# 4ButtonSwitch_Rev1.net
KiCad netlist of a schematic drawn in EAGLE
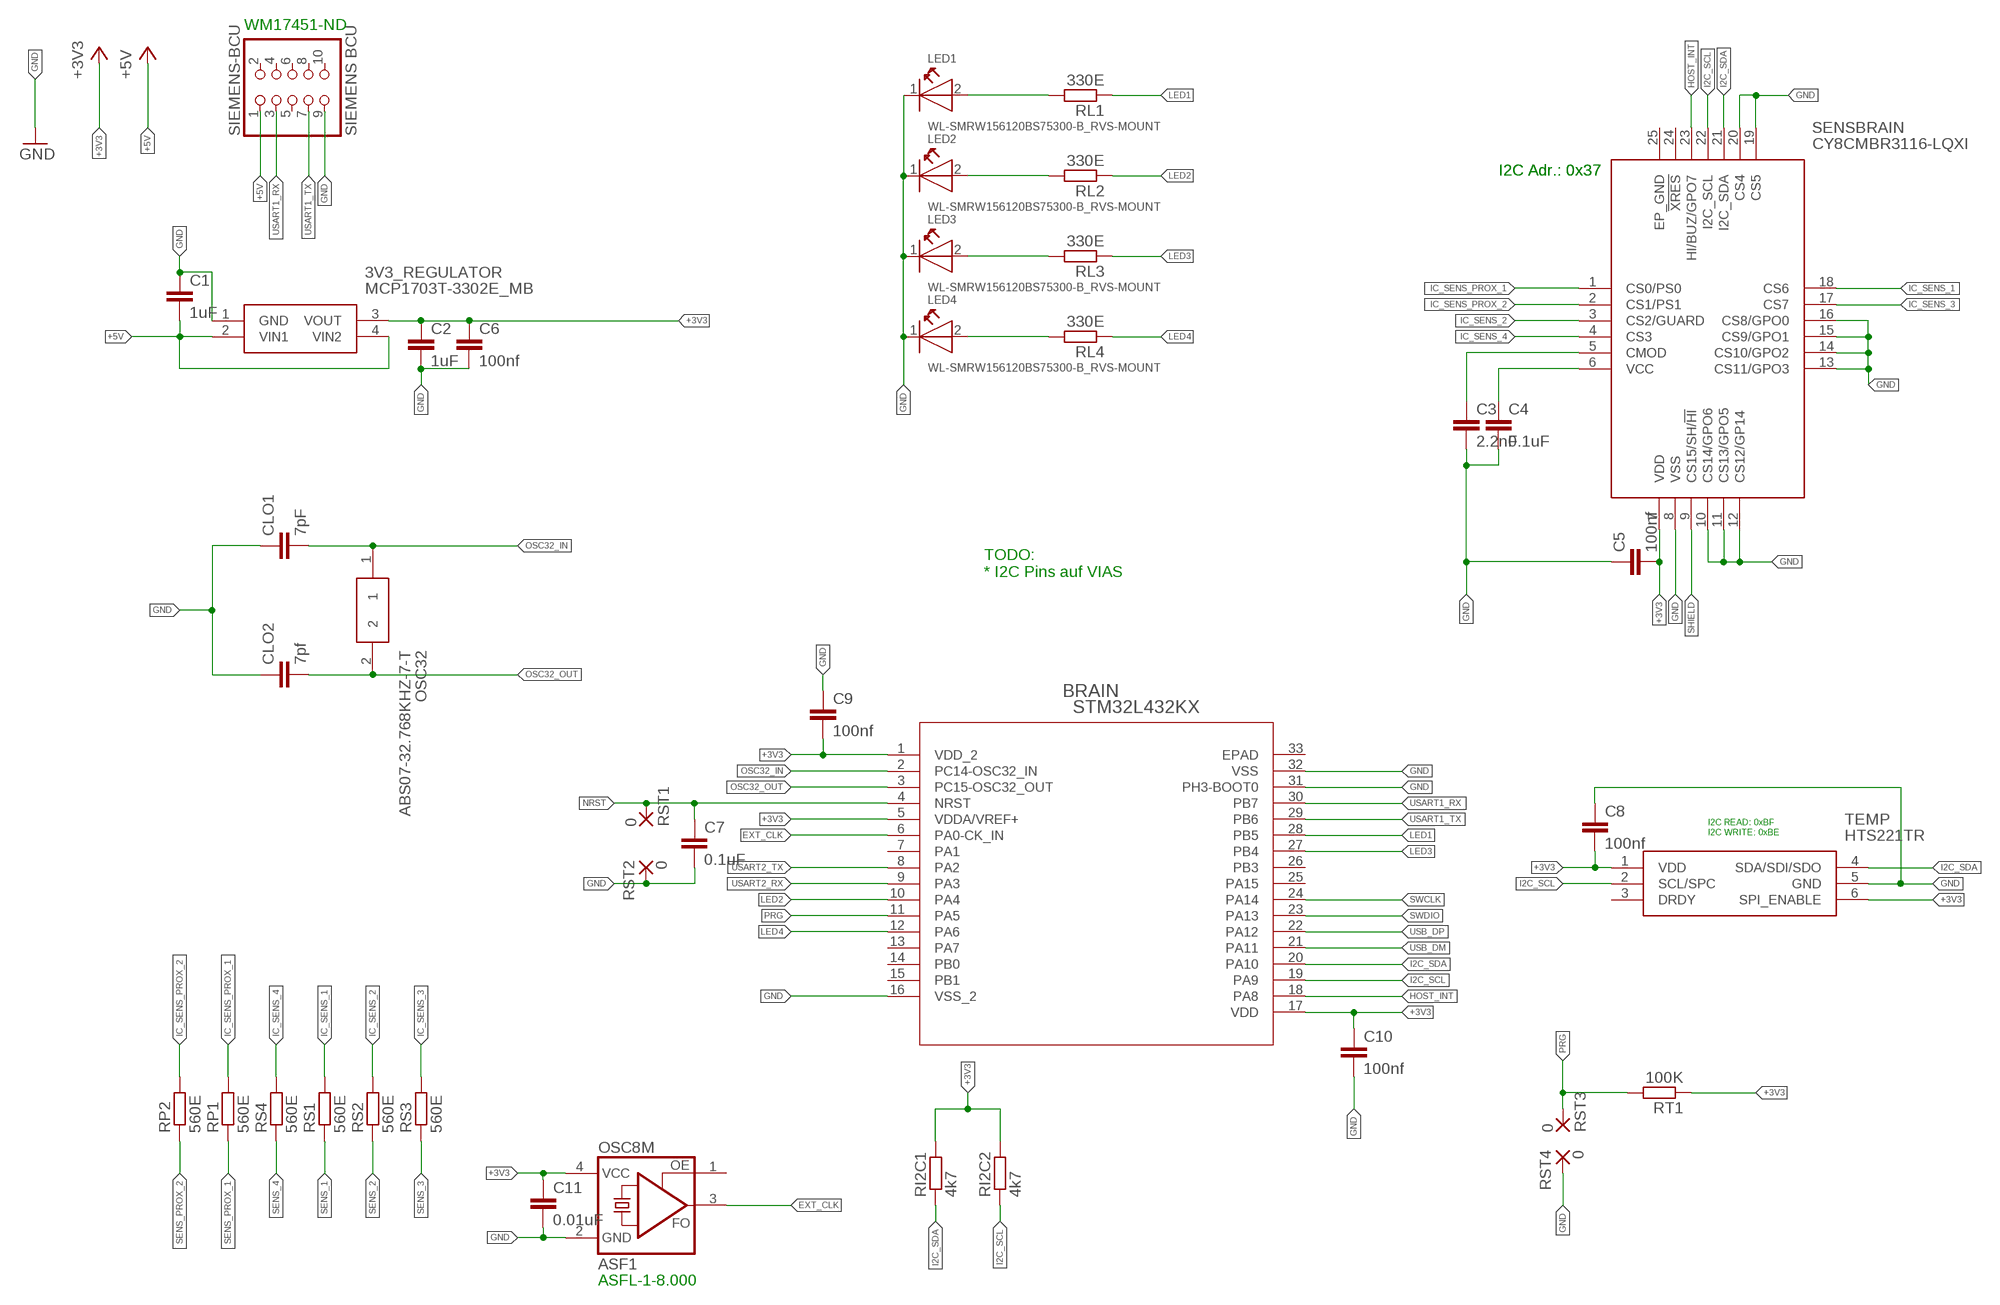
[diagram p0: schematic, sheet 1]

(export (version "E")
  (design (tool "Eeschema 10.0.6"))
  (components
    (comp (ref "3V3_REGULATOR")
      (value "MCP1703T-3302E_MB")
      (footprint "eagle-import:SOT-89(MB)")
      (fields
        (field (name "ARROW_PART_NUMBER") "MCP1703T-3302E/MB")
        (field (name "RS_PART_NUMBER") "9122916")
      )
      (libsource (lib "eagle-import") (part "MCP1703T-3302E_MB"))
    )
    (comp (ref "BRAIN")
      (value "STM32L432KX")
      (footprint "eagle-import:UFQFPN32-5X5MM")
      (fields (field (name "MANUFACTURER_PART_NUMBER") "stm32l432kx"))
      (libsource (lib "eagle-import") (part "STM32L432KX"))
    )
    (comp (ref "C1")
      (value "1uF")
      (footprint "eagle-import:C0402")
      (libsource (lib "eagle-import") (part "C-EUC0402"))
    )
    (comp (ref "C2")
      (value "1uF")
      (footprint "eagle-import:C0402")
      (libsource (lib "eagle-import") (part "C-EUC0402"))
    )
    (comp (ref "C3")
      (value "2.2nF")
      (footprint "eagle-import:C0402")
      (libsource (lib "eagle-import") (part "C-EUC0402"))
    )
    (comp (ref "C4")
      (value "0.1uF")
      (footprint "eagle-import:C0402")
      (libsource (lib "eagle-import") (part "C-EUC0402"))
    )
    (comp (ref "C5")
      (value "100nf")
      (footprint "eagle-import:C0402")
      (libsource (lib "eagle-import") (part "C-EUC0402"))
    )
    (comp (ref "C6")
      (value "100nf")
      (footprint "eagle-import:C0402")
      (libsource (lib "eagle-import") (part "C-EUC0402"))
    )
    (comp (ref "C7")
      (value "0.1uF")
      (footprint "eagle-import:C0402")
      (libsource (lib "eagle-import") (part "C-EUC0402"))
    )
    (comp (ref "C8")
      (value "100nf")
      (footprint "eagle-import:C0402")
      (libsource (lib "eagle-import") (part "C-EUC0402"))
    )
    (comp (ref "C9")
      (value "100nf")
      (footprint "eagle-import:C0402")
      (libsource (lib "eagle-import") (part "C-EUC0402"))
    )
    (comp (ref "C10")
      (value "100nf")
      (footprint "eagle-import:C0402")
      (libsource (lib "eagle-import") (part "C-EUC0402"))
    )
    (comp (ref "C11")
      (value "0.01uF")
      (footprint "eagle-import:C0402")
      (libsource (lib "eagle-import") (part "C-EUC0402"))
    )
    (comp (ref "CLO1")
      (value "7pF")
      (footprint "eagle-import:C0402")
      (libsource (lib "eagle-import") (part "C-EUC0402"))
    )
    (comp (ref "CLO2")
      (value "7pf")
      (footprint "eagle-import:C0402")
      (libsource (lib "eagle-import") (part "C-EUC0402"))
    )
    (comp (ref "LED1")
      (value "WL-SMRW156120BS75300-B_RVS-MOUNT")
      (footprint "eagle-import:WL-SMRW-1206-CYLDR-REVERSE-MOUNT")
      (libsource (lib "eagle-import") (part "WL-SMRW156120BS75300-B_RVS-MOUNT"))
    )
    (comp (ref "LED2")
      (value "WL-SMRW156120BS75300-B_RVS-MOUNT")
      (footprint "eagle-import:WL-SMRW-1206-CYLDR-REVERSE-MOUNT")
      (libsource (lib "eagle-import") (part "WL-SMRW156120BS75300-B_RVS-MOUNT"))
    )
    (comp (ref "LED3")
      (value "WL-SMRW156120BS75300-B_RVS-MOUNT")
      (footprint "eagle-import:WL-SMRW-1206-CYLDR-REVERSE-MOUNT")
      (libsource (lib "eagle-import") (part "WL-SMRW156120BS75300-B_RVS-MOUNT"))
    )
    (comp (ref "LED4")
      (value "WL-SMRW156120BS75300-B_RVS-MOUNT")
      (footprint "eagle-import:WL-SMRW-1206-CYLDR-REVERSE-MOUNT")
      (libsource (lib "eagle-import") (part "WL-SMRW156120BS75300-B_RVS-MOUNT"))
    )
    (comp (ref "OSC8M")
      (value "ASF1")
      (footprint "eagle-import:ASF")
      (libsource (lib "eagle-import") (part "ASF1"))
    )
    (comp (ref "OSC32")
      (value "ABS07-32.768KHZ-7-T")
      (footprint "eagle-import:ABS-07")
      (fields (field (name "RS_PART_NUMBER") "1712773P"))
      (libsource (lib "eagle-import") (part "ABS07-32.768KHZ-7-T"))
    )
    (comp (ref "RI2C1")
      (value "4k7")
      (footprint "eagle-import:R0402")
      (libsource (lib "eagle-import") (part "R-EU_R0402"))
    )
    (comp (ref "RI2C2")
      (value "4k7")
      (footprint "eagle-import:R0402")
      (libsource (lib "eagle-import") (part "R-EU_R0402"))
    )
    (comp (ref "RL1")
      (value "330E")
      (footprint "eagle-import:R0402")
      (libsource (lib "eagle-import") (part "R-EU_R0402"))
    )
    (comp (ref "RL2")
      (value "330E")
      (footprint "eagle-import:R0402")
      (libsource (lib "eagle-import") (part "R-EU_R0402"))
    )
    (comp (ref "RL3")
      (value "330E")
      (footprint "eagle-import:R0402")
      (libsource (lib "eagle-import") (part "R-EU_R0402"))
    )
    (comp (ref "RL4")
      (value "330E")
      (footprint "eagle-import:R0402")
      (libsource (lib "eagle-import") (part "R-EU_R0402"))
    )
    (comp (ref "RP1")
      (value "560E")
      (footprint "eagle-import:R0402")
      (libsource (lib "eagle-import") (part "R-EU_R0402"))
    )
    (comp (ref "RP2")
      (value "560E")
      (footprint "eagle-import:R0402")
      (libsource (lib "eagle-import") (part "R-EU_R0402"))
    )
    (comp (ref "RS1")
      (value "560E")
      (footprint "eagle-import:R0402")
      (libsource (lib "eagle-import") (part "R-EU_R0402"))
    )
    (comp (ref "RS2")
      (value "560E")
      (footprint "eagle-import:R0402")
      (libsource (lib "eagle-import") (part "R-EU_R0402"))
    )
    (comp (ref "RS3")
      (value "560E")
      (footprint "eagle-import:R0402")
      (libsource (lib "eagle-import") (part "R-EU_R0402"))
    )
    (comp (ref "RS4")
      (value "560E")
      (footprint "eagle-import:R0402")
      (libsource (lib "eagle-import") (part "R-EU_R0402"))
    )
    (comp (ref "RST1")
      (value "0")
      (footprint "eagle-import:SMD2,54-5,08")
      (libsource (lib "eagle-import") (part "SMD5"))
    )
    (comp (ref "RST2")
      (value "0")
      (footprint "eagle-import:SMD2,54-5,08")
      (libsource (lib "eagle-import") (part "SMD5"))
    )
    (comp (ref "RST3")
      (value "0")
      (footprint "eagle-import:SMD2,54-5,08")
      (libsource (lib "eagle-import") (part "SMD5"))
    )
    (comp (ref "RST4")
      (value "0")
      (footprint "eagle-import:SMD2,54-5,08")
      (libsource (lib "eagle-import") (part "SMD5"))
    )
    (comp (ref "RT1")
      (value "100K")
      (footprint "eagle-import:R0402")
      (libsource (lib "eagle-import") (part "R-EU_R0402"))
    )
    (comp (ref "SENSBRAIN")
      (value "CY8CMBR3116-LQXI")
      (footprint "eagle-import:QFN50P400X400X60-25N")
      (fields (field (name "RS_PART_NUMBER") "1242976P"))
      (libsource (lib "eagle-import") (part "CY8CMBR3116-LQXI"))
    )
    (comp (ref "SIEMENS-BCU")
      (value "SIEMENS BCU")
      (footprint "eagle-import:2X05SMD")
      (libsource (lib "eagle-import") (part "PINHD-2X5_2.54-SMD"))
    )
    (comp (ref "TEMP")
      (value "HTS221TR")
      (footprint "eagle-import:HLGA-6L")
      (fields (field (name "RS_PART_NUMBER") "1660935"))
      (libsource (lib "eagle-import") (part "HTS221TR"))
    )
  )
  (nets
    (net (code "1") (name "+3V3") (class "Default")
      (node (ref "3V3_REGULATOR") (pin "3") (pinfunction "VOUT_3") (pintype "bidirectional"))
      (node (ref "BRAIN") (pin "1") (pinfunction "VDD_2_1") (pintype "power_in"))
      (node (ref "BRAIN") (pin "17") (pinfunction "VDD_17") (pintype "power_in"))
      (node (ref "BRAIN") (pin "5") (pinfunction "VDDA/VREF+_5") (pintype "power_in"))
      (node (ref "C10") (pin "1") (pinfunction "1_1") (pintype "passive"))
      (node (ref "C11") (pin "1") (pinfunction "1_1") (pintype "passive"))
      (node (ref "C2") (pin "1") (pinfunction "1_1") (pintype "passive"))
      (node (ref "C5") (pin "2") (pinfunction "2_2") (pintype "passive"))
      (node (ref "C6") (pin "1") (pinfunction "1_1") (pintype "passive"))
      (node (ref "C8") (pin "2") (pinfunction "2_2") (pintype "passive"))
      (node (ref "C9") (pin "2") (pinfunction "2_2") (pintype "passive"))
      (node (ref "OSC8M") (pin "4") (pinfunction "VCC_4") (pintype "power_in"))
      (node (ref "RI2C1") (pin "2") (pinfunction "2_2") (pintype "passive"))
      (node (ref "RI2C2") (pin "2") (pinfunction "2_2") (pintype "passive"))
      (node (ref "RT1") (pin "1") (pinfunction "1_1") (pintype "passive"))
      (node (ref "SENSBRAIN") (pin "7") (pinfunction "VDD_7") (pintype "power_in"))
      (node (ref "TEMP") (pin "1") (pinfunction "VDD_1") (pintype "bidirectional"))
      (node (ref "TEMP") (pin "6") (pinfunction "SPI_ENABLE_6") (pintype "bidirectional"))
    )
    (net (code "2") (name "+5V") (class "Default")
      (node (ref "3V3_REGULATOR") (pin "2") (pinfunction "VIN1_2") (pintype "bidirectional"))
      (node (ref "3V3_REGULATOR") (pin "4") (pinfunction "VIN2_4") (pintype "bidirectional"))
      (node (ref "C1") (pin "2") (pinfunction "2_2") (pintype "passive"))
      (node (ref "SIEMENS-BCU") (pin "1") (pinfunction "1_1") (pintype "passive"))
    )
    (net (code "3") (name "/EP_GND") (class "Default")
      (node (ref "SENSBRAIN") (pin "25") (pinfunction "EP_GND_25") (pintype "power_in"))
    )
    (net (code "4") (name "EXT_CLK") (class "Default")
      (node (ref "BRAIN") (pin "6") (pinfunction "PA0-CK_IN_6") (pintype "bidirectional"))
      (node (ref "OSC8M") (pin "3") (pinfunction "FO_3") (pintype "output"))
    )
    (net (code "5") (name "GND") (class "Default")
      (node (ref "3V3_REGULATOR") (pin "1") (pinfunction "GND_1") (pintype "bidirectional"))
      (node (ref "BRAIN") (pin "16") (pinfunction "VSS_2_16") (pintype "power_in"))
      (node (ref "BRAIN") (pin "31") (pinfunction "PH3-BOOT0_31") (pintype "bidirectional"))
      (node (ref "BRAIN") (pin "32") (pinfunction "VSS_32") (pintype "power_in"))
      (node (ref "C1") (pin "1") (pinfunction "1_1") (pintype "passive"))
      (node (ref "C10") (pin "2") (pinfunction "2_2") (pintype "passive"))
      (node (ref "C11") (pin "2") (pinfunction "2_2") (pintype "passive"))
      (node (ref "C2") (pin "2") (pinfunction "2_2") (pintype "passive"))
      (node (ref "C3") (pin "2") (pinfunction "2_2") (pintype "passive"))
      (node (ref "C4") (pin "2") (pinfunction "2_2") (pintype "passive"))
      (node (ref "C5") (pin "1") (pinfunction "1_1") (pintype "passive"))
      (node (ref "C6") (pin "2") (pinfunction "2_2") (pintype "passive"))
      (node (ref "C7") (pin "2") (pinfunction "2_2") (pintype "passive"))
      (node (ref "C8") (pin "1") (pinfunction "1_1") (pintype "passive"))
      (node (ref "C9") (pin "1") (pinfunction "1_1") (pintype "passive"))
      (node (ref "CLO1") (pin "1") (pinfunction "1_1") (pintype "passive"))
      (node (ref "CLO2") (pin "1") (pinfunction "1_1") (pintype "passive"))
      (node (ref "LED1") (pin "1") (pinfunction "K_1") (pintype "bidirectional"))
      (node (ref "LED2") (pin "1") (pinfunction "K_1") (pintype "bidirectional"))
      (node (ref "LED3") (pin "1") (pinfunction "K_1") (pintype "bidirectional"))
      (node (ref "LED4") (pin "1") (pinfunction "K_1") (pintype "bidirectional"))
      (node (ref "OSC8M") (pin "2") (pinfunction "GND_2") (pintype "power_in"))
      (node (ref "RST2") (pin "1") (pinfunction "P_1") (pintype "passive"))
      (node (ref "RST4") (pin "1") (pinfunction "P_1") (pintype "passive"))
      (node (ref "SENSBRAIN") (pin "10") (pinfunction "CS14/GPO6_10") (pintype "input"))
      (node (ref "SENSBRAIN") (pin "11") (pinfunction "CS13/GPO5_11") (pintype "input"))
      (node (ref "SENSBRAIN") (pin "12") (pinfunction "CS12/GP14_12") (pintype "input"))
      (node (ref "SENSBRAIN") (pin "13") (pinfunction "CS11/GPO3_13") (pintype "input"))
      (node (ref "SENSBRAIN") (pin "14") (pinfunction "CS10/GPO2_14") (pintype "input"))
      (node (ref "SENSBRAIN") (pin "15") (pinfunction "CS9/GPO1_15") (pintype "input"))
      (node (ref "SENSBRAIN") (pin "16") (pinfunction "CS8/GPO0_16") (pintype "input"))
      (node (ref "SENSBRAIN") (pin "19") (pinfunction "CS5_19") (pintype "input"))
      (node (ref "SENSBRAIN") (pin "20") (pinfunction "CS4_20") (pintype "input"))
      (node (ref "SENSBRAIN") (pin "8") (pinfunction "VSS_8") (pintype "power_in"))
      (node (ref "SIEMENS-BCU") (pin "9") (pinfunction "9_9") (pintype "passive"))
      (node (ref "TEMP") (pin "5") (pinfunction "GND_5") (pintype "bidirectional"))
    )
    (net (code "6") (name "HOST_INT") (class "Default")
      (node (ref "BRAIN") (pin "18") (pinfunction "PA8_18") (pintype "bidirectional"))
      (node (ref "SENSBRAIN") (pin "23") (pinfunction "HI/BUZ/GPO7_23") (pintype "bidirectional"))
    )
    (net (code "7") (name "I2C_SCL") (class "Default")
      (node (ref "BRAIN") (pin "19") (pinfunction "PA9_19") (pintype "bidirectional"))
      (node (ref "RI2C2") (pin "1") (pinfunction "1_1") (pintype "passive"))
      (node (ref "SENSBRAIN") (pin "22") (pinfunction "I2C_SCL_22") (pintype "bidirectional"))
      (node (ref "TEMP") (pin "2") (pinfunction "SCL/SPC_2") (pintype "bidirectional"))
    )
    (net (code "8") (name "I2C_SDA") (class "Default")
      (node (ref "BRAIN") (pin "20") (pinfunction "PA10_20") (pintype "bidirectional"))
      (node (ref "RI2C1") (pin "1") (pinfunction "1_1") (pintype "passive"))
      (node (ref "SENSBRAIN") (pin "21") (pinfunction "I2C_SDA_21") (pintype "bidirectional"))
      (node (ref "TEMP") (pin "4") (pinfunction "SDA/SDI/SDO_4") (pintype "bidirectional"))
    )
    (net (code "9") (name "IC_SENS_1") (class "Default")
      (node (ref "RS1") (pin "2") (pinfunction "2_2") (pintype "passive"))
      (node (ref "SENSBRAIN") (pin "18") (pinfunction "CS6_18") (pintype "input"))
    )
    (net (code "10") (name "IC_SENS_2") (class "Default")
      (node (ref "RS2") (pin "2") (pinfunction "2_2") (pintype "passive"))
      (node (ref "SENSBRAIN") (pin "3") (pinfunction "CS2/GUARD_3") (pintype "input"))
    )
    (net (code "11") (name "IC_SENS_3") (class "Default")
      (node (ref "RS3") (pin "2") (pinfunction "2_2") (pintype "passive"))
      (node (ref "SENSBRAIN") (pin "17") (pinfunction "CS7_17") (pintype "input"))
    )
    (net (code "12") (name "IC_SENS_4") (class "Default")
      (node (ref "RS4") (pin "2") (pinfunction "2_2") (pintype "passive"))
      (node (ref "SENSBRAIN") (pin "4") (pinfunction "CS3_4") (pintype "input"))
    )
    (net (code "13") (name "IC_SENS_PROX_1") (class "Default")
      (node (ref "RP1") (pin "2") (pinfunction "2_2") (pintype "passive"))
      (node (ref "SENSBRAIN") (pin "1") (pinfunction "CS0/PS0_1") (pintype "input"))
    )
    (net (code "14") (name "IC_SENS_PROX_2") (class "Default")
      (node (ref "RP2") (pin "2") (pinfunction "2_2") (pintype "passive"))
      (node (ref "SENSBRAIN") (pin "2") (pinfunction "CS1/PS1_2") (pintype "input"))
    )
    (net (code "15") (name "LED1") (class "Default")
      (node (ref "BRAIN") (pin "28") (pinfunction "PB5_28") (pintype "bidirectional"))
      (node (ref "RL1") (pin "1") (pinfunction "1_1") (pintype "passive"))
    )
    (net (code "16") (name "LED2") (class "Default")
      (node (ref "BRAIN") (pin "10") (pinfunction "PA4_10") (pintype "bidirectional"))
      (node (ref "RL2") (pin "1") (pinfunction "1_1") (pintype "passive"))
    )
    (net (code "17") (name "LED3") (class "Default")
      (node (ref "BRAIN") (pin "27") (pinfunction "PB4_27") (pintype "bidirectional"))
      (node (ref "RL3") (pin "1") (pinfunction "1_1") (pintype "passive"))
    )
    (net (code "18") (name "LED4") (class "Default")
      (node (ref "BRAIN") (pin "12") (pinfunction "PA6_12") (pintype "bidirectional"))
      (node (ref "RL4") (pin "1") (pinfunction "1_1") (pintype "passive"))
    )
    (net (code "19") (name "NRST") (class "Default")
      (node (ref "BRAIN") (pin "4") (pinfunction "NRST_4") (pintype "bidirectional"))
      (node (ref "C7") (pin "1") (pinfunction "1_1") (pintype "passive"))
      (node (ref "RST1") (pin "1") (pinfunction "P_1") (pintype "passive"))
    )
    (net (code "20") (name "Net-(LED1-A)") (class "Default")
      (node (ref "LED1") (pin "2") (pinfunction "A_2") (pintype "bidirectional"))
      (node (ref "RL1") (pin "2") (pinfunction "2_2") (pintype "passive"))
    )
    (net (code "21") (name "Net-(LED2-A)") (class "Default")
      (node (ref "LED2") (pin "2") (pinfunction "A_2") (pintype "bidirectional"))
      (node (ref "RL2") (pin "2") (pinfunction "2_2") (pintype "passive"))
    )
    (net (code "22") (name "Net-(LED3-A)") (class "Default")
      (node (ref "LED3") (pin "2") (pinfunction "A_2") (pintype "bidirectional"))
      (node (ref "RL3") (pin "2") (pinfunction "2_2") (pintype "passive"))
    )
    (net (code "23") (name "Net-(LED4-A)") (class "Default")
      (node (ref "LED4") (pin "2") (pinfunction "A_2") (pintype "bidirectional"))
      (node (ref "RL4") (pin "2") (pinfunction "2_2") (pintype "passive"))
    )
    (net (code "24") (name "Net-(SENSBRAIN-CMOD)") (class "Default")
      (node (ref "C3") (pin "1") (pinfunction "1_1") (pintype "passive"))
      (node (ref "SENSBRAIN") (pin "5") (pinfunction "CMOD_5") (pintype "bidirectional"))
    )
    (net (code "25") (name "Net-(SENSBRAIN-VCC)") (class "Default")
      (node (ref "C4") (pin "1") (pinfunction "1_1") (pintype "passive"))
      (node (ref "SENSBRAIN") (pin "6") (pinfunction "VCC_6") (pintype "power_in"))
    )
    (net (code "26") (name "OSC32_IN") (class "Default")
      (node (ref "BRAIN") (pin "2") (pinfunction "PC14-OSC32_IN_2") (pintype "bidirectional"))
      (node (ref "CLO1") (pin "2") (pinfunction "2_2") (pintype "passive"))
      (node (ref "OSC32") (pin "1") (pinfunction "1_1") (pintype "bidirectional"))
    )
    (net (code "27") (name "OSC32_OUT") (class "Default")
      (node (ref "BRAIN") (pin "3") (pinfunction "PC15-OSC32_OUT_3") (pintype "bidirectional"))
      (node (ref "CLO2") (pin "2") (pinfunction "2_2") (pintype "passive"))
      (node (ref "OSC32") (pin "2") (pinfunction "2_2") (pintype "bidirectional"))
    )
    (net (code "28") (name "PRG") (class "Default")
      (node (ref "BRAIN") (pin "11") (pinfunction "PA5_11") (pintype "bidirectional"))
      (node (ref "RST3") (pin "1") (pinfunction "P_1") (pintype "passive"))
      (node (ref "RT1") (pin "2") (pinfunction "2_2") (pintype "passive"))
    )
    (net (code "29") (name "SENS_1") (class "Default")
      (node (ref "RS1") (pin "1") (pinfunction "1_1") (pintype "passive"))
    )
    (net (code "30") (name "SENS_2") (class "Default")
      (node (ref "RS2") (pin "1") (pinfunction "1_1") (pintype "passive"))
    )
    (net (code "31") (name "SENS_3") (class "Default")
      (node (ref "RS3") (pin "1") (pinfunction "1_1") (pintype "passive"))
    )
    (net (code "32") (name "SENS_4") (class "Default")
      (node (ref "RS4") (pin "1") (pinfunction "1_1") (pintype "passive"))
    )
    (net (code "33") (name "SENS_PROX_1") (class "Default")
      (node (ref "RP1") (pin "1") (pinfunction "1_1") (pintype "passive"))
    )
    (net (code "34") (name "SENS_PROX_2") (class "Default")
      (node (ref "RP2") (pin "1") (pinfunction "1_1") (pintype "passive"))
    )
    (net (code "35") (name "SHIELD") (class "Default")
      (node (ref "SENSBRAIN") (pin "9") (pinfunction "CS15/SH/~{HI}_9") (pintype "input"))
    )
    (net (code "36") (name "SWCLK") (class "Default")
      (node (ref "BRAIN") (pin "24") (pinfunction "PA14_24") (pintype "bidirectional"))
    )
    (net (code "37") (name "SWDIO") (class "Default")
      (node (ref "BRAIN") (pin "23") (pinfunction "PA13_23") (pintype "bidirectional"))
    )
    (net (code "38") (name "USART1_RX") (class "Default")
      (node (ref "BRAIN") (pin "30") (pinfunction "PB7_30") (pintype "bidirectional"))
      (node (ref "SIEMENS-BCU") (pin "3") (pinfunction "3_3") (pintype "passive"))
    )
    (net (code "39") (name "USART1_TX") (class "Default")
      (node (ref "BRAIN") (pin "29") (pinfunction "PB6_29") (pintype "bidirectional"))
      (node (ref "SIEMENS-BCU") (pin "7") (pinfunction "7_7") (pintype "passive"))
    )
    (net (code "40") (name "USART2_RX") (class "Default")
      (node (ref "BRAIN") (pin "9") (pinfunction "PA3_9") (pintype "bidirectional"))
    )
    (net (code "41") (name "USART2_TX") (class "Default")
      (node (ref "BRAIN") (pin "8") (pinfunction "PA2_8") (pintype "bidirectional"))
    )
    (net (code "42") (name "USB_DM") (class "Default")
      (node (ref "BRAIN") (pin "21") (pinfunction "PA11_21") (pintype "bidirectional"))
    )
    (net (code "43") (name "USB_DP") (class "Default")
      (node (ref "BRAIN") (pin "22") (pinfunction "PA12_22") (pintype "bidirectional"))
    )
    (net (code "44") (name "unconnected-(BRAIN-EPAD-Pad33)") (class "Default")
      (node (ref "BRAIN") (pin "33") (pinfunction "EPAD_33") (pintype "passive"))
    )
    (net (code "45") (name "unconnected-(BRAIN-PA1-Pad7)") (class "Default")
      (node (ref "BRAIN") (pin "7") (pinfunction "PA1_7") (pintype "bidirectional"))
    )
    (net (code "46") (name "unconnected-(BRAIN-PA7-Pad13)") (class "Default")
      (node (ref "BRAIN") (pin "13") (pinfunction "PA7_13") (pintype "bidirectional"))
    )
    (net (code "47") (name "unconnected-(BRAIN-PA15-Pad25)") (class "Default")
      (node (ref "BRAIN") (pin "25") (pinfunction "PA15_25") (pintype "bidirectional"))
    )
    (net (code "48") (name "unconnected-(BRAIN-PB0-Pad14)") (class "Default")
      (node (ref "BRAIN") (pin "14") (pinfunction "PB0_14") (pintype "bidirectional"))
    )
    (net (code "49") (name "unconnected-(BRAIN-PB1-Pad15)") (class "Default")
      (node (ref "BRAIN") (pin "15") (pinfunction "PB1_15") (pintype "bidirectional"))
    )
    (net (code "50") (name "unconnected-(BRAIN-PB3-Pad26)") (class "Default")
      (node (ref "BRAIN") (pin "26") (pinfunction "PB3_26") (pintype "bidirectional"))
    )
    (net (code "51") (name "unconnected-(OSC8M-OE-Pad1)") (class "Default")
      (node (ref "OSC8M") (pin "1") (pinfunction "OE_1") (pintype "input"))
    )
    (net (code "52") (name "unconnected-(SENSBRAIN-~{XRES}-Pad24)") (class "Default")
      (node (ref "SENSBRAIN") (pin "24") (pinfunction "~{XRES}_24") (pintype "bidirectional"))
    )
    (net (code "53") (name "unconnected-(SIEMENS-BCU-Pad2)") (class "Default")
      (node (ref "SIEMENS-BCU") (pin "2") (pinfunction "2_2") (pintype "passive"))
    )
    (net (code "54") (name "unconnected-(SIEMENS-BCU-Pad4)") (class "Default")
      (node (ref "SIEMENS-BCU") (pin "4") (pinfunction "4_4") (pintype "passive"))
    )
    (net (code "55") (name "unconnected-(SIEMENS-BCU-Pad5)") (class "Default")
      (node (ref "SIEMENS-BCU") (pin "5") (pinfunction "5_5") (pintype "passive"))
    )
    (net (code "56") (name "unconnected-(SIEMENS-BCU-Pad6)") (class "Default")
      (node (ref "SIEMENS-BCU") (pin "6") (pinfunction "6_6") (pintype "passive"))
    )
    (net (code "57") (name "unconnected-(SIEMENS-BCU-Pad8)") (class "Default")
      (node (ref "SIEMENS-BCU") (pin "8") (pinfunction "8_8") (pintype "passive"))
    )
    (net (code "58") (name "unconnected-(SIEMENS-BCU-Pad10)") (class "Default")
      (node (ref "SIEMENS-BCU") (pin "10") (pinfunction "10_10") (pintype "passive"))
    )
    (net (code "59") (name "unconnected-(TEMP-DRDY-Pad3)") (class "Default")
      (node (ref "TEMP") (pin "3") (pinfunction "DRDY_3") (pintype "bidirectional"))
    )
  )
)
